# 260116710xxxx-HW-V2_0.net
KiCad netlist of a schematic drawn in EAGLE
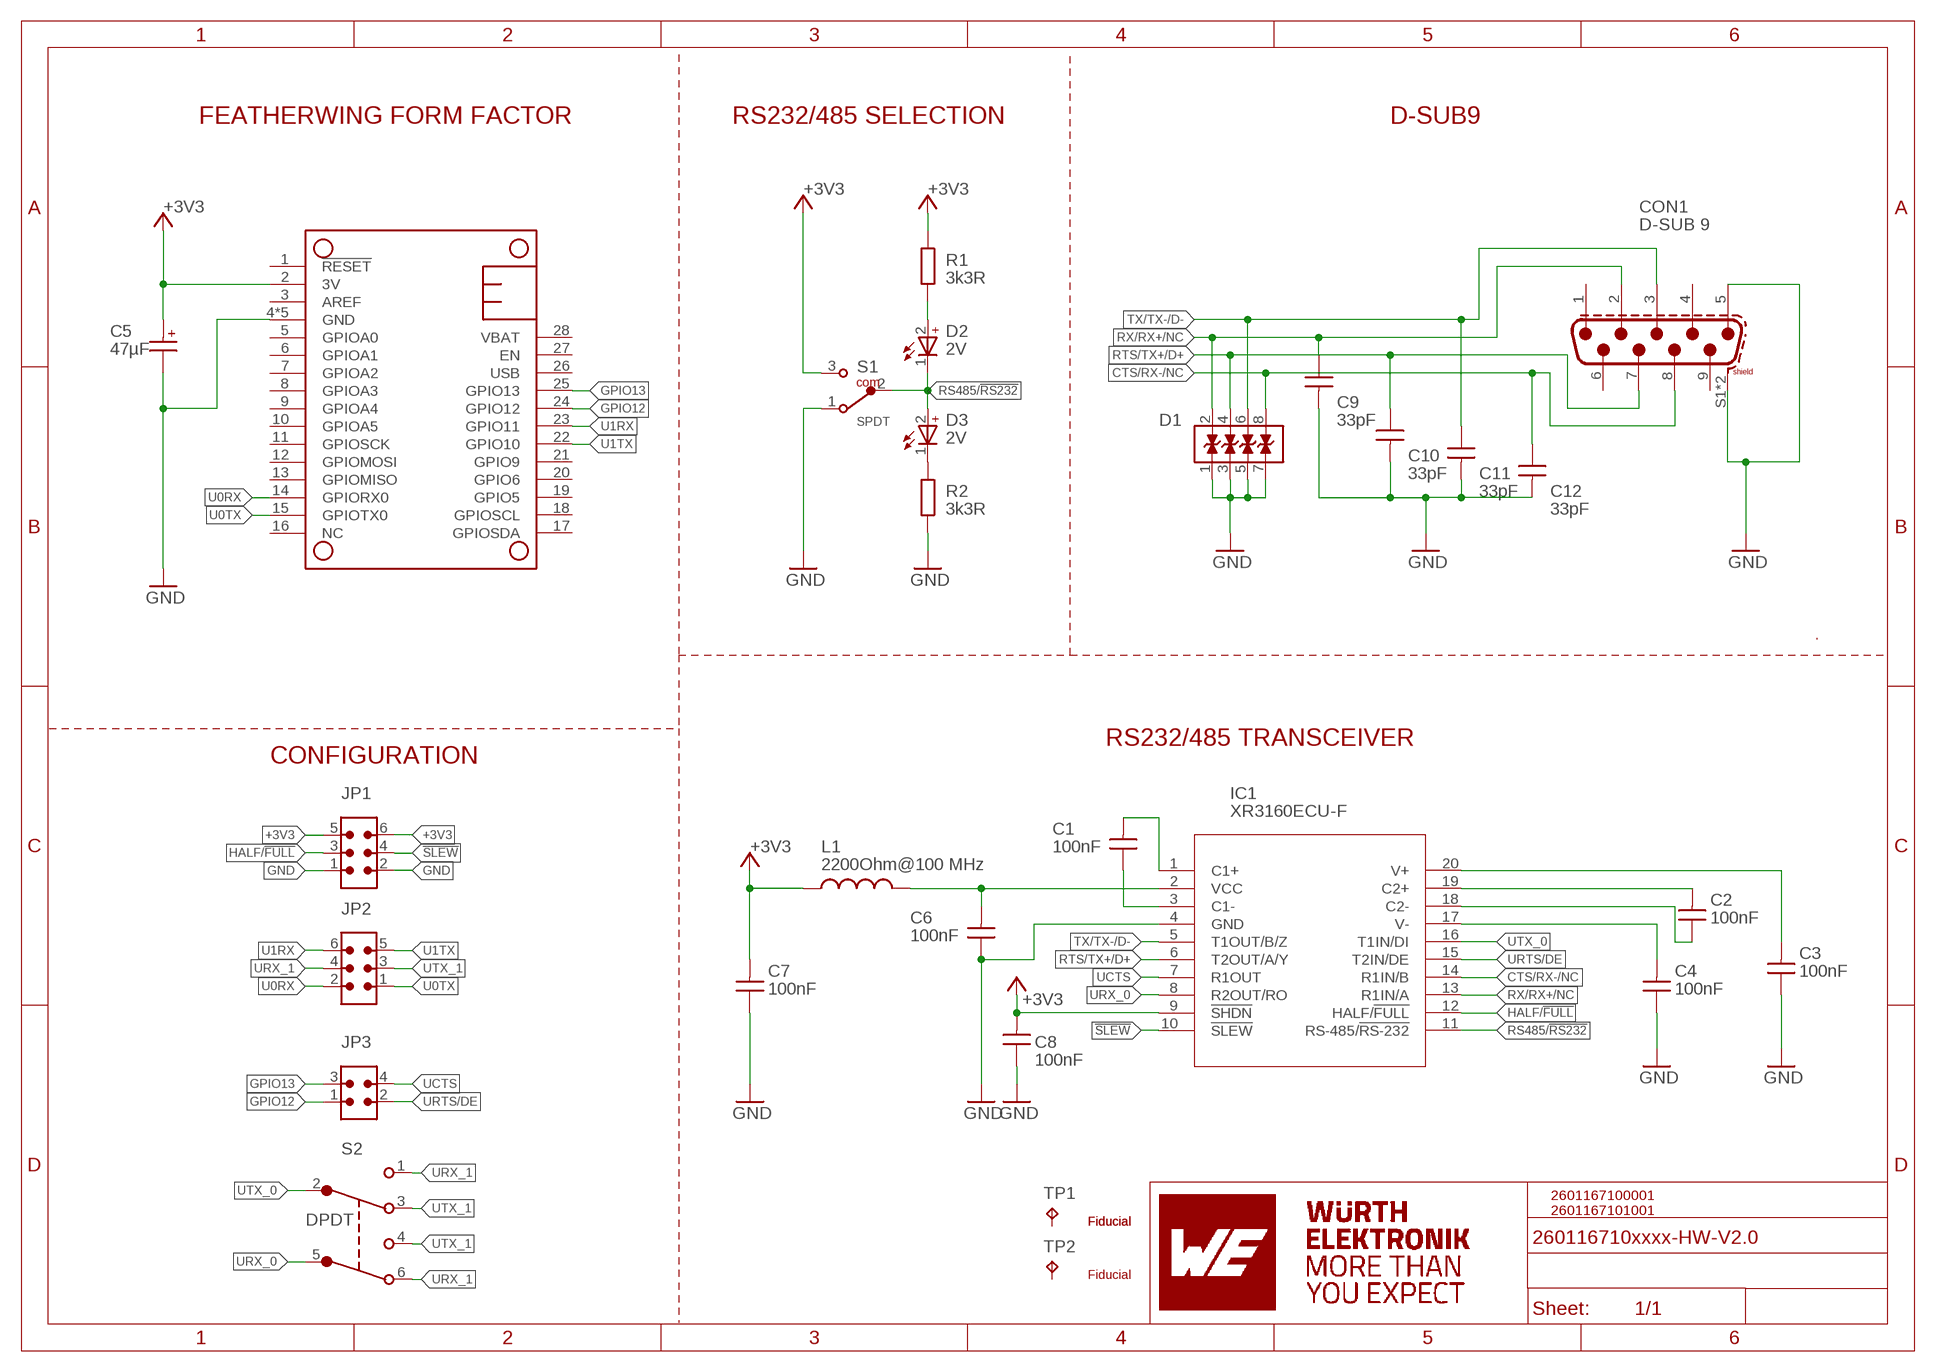
[diagram p0: schematic, sheet 1]

(export (version "E")
  (design (tool "Eeschema 10.0.6"))
  (components
    (comp (ref "C1")
      (value "100nF")
      (footprint "eagle-import:WCAP-CSGP_0603_W")
      (libsource (lib "eagle-import") (part "WCAP-CSGP_Rev21e_WCAP-CSGP_0603_10V(DC)_W_885012206020"))
    )
    (comp (ref "C2")
      (value "100nF")
      (footprint "eagle-import:WCAP-CSGP_0603_W")
      (libsource (lib "eagle-import") (part "WCAP-CSGP_Rev21e_WCAP-CSGP_0603_10V(DC)_W_885012206020"))
    )
    (comp (ref "C3")
      (value "100nF")
      (footprint "eagle-import:WCAP-CSGP_0603_W")
      (libsource (lib "eagle-import") (part "WCAP-CSGP_Rev21e_WCAP-CSGP_0603_10V(DC)_W_885012206020"))
    )
    (comp (ref "C4")
      (value "100nF")
      (footprint "eagle-import:WCAP-CSGP_0603_W")
      (libsource (lib "eagle-import") (part "WCAP-CSGP_Rev21e_WCAP-CSGP_0603_10V(DC)_W_885012206020"))
    )
    (comp (ref "C5")
      (value "47µF")
      (footprint "eagle-import:WCAP-AS5H_5X5.5(DXL)")
      (libsource (lib "eagle-import") (part "WCAP-AS5H_5X5.5_865230142003"))
    )
    (comp (ref "C6")
      (value "100nF")
      (footprint "eagle-import:WCAP-CSGP_0603_W")
      (libsource (lib "eagle-import") (part "WCAP-CSGP_Rev21e_WCAP-CSGP_0603_10V(DC)_W_885012206020"))
    )
    (comp (ref "C7")
      (value "100nF")
      (footprint "eagle-import:WCAP-CSGP_0603_W")
      (libsource (lib "eagle-import") (part "WCAP-CSGP_Rev21e_WCAP-CSGP_0603_10V(DC)_W_885012206020"))
    )
    (comp (ref "C8")
      (value "100nF")
      (footprint "eagle-import:WCAP-CSGP_0603_W")
      (libsource (lib "eagle-import") (part "WCAP-CSGP_Rev21e_WCAP-CSGP_0603_10V(DC)_W_885012206020"))
    )
    (comp (ref "C9")
      (value "33pF")
      (footprint "eagle-import:WCAP-CSGP_0603_W")
      (libsource (lib "eagle-import") (part "WCAP-CSGP_0603_25V(DC)_W_885012006035"))
    )
    (comp (ref "C10")
      (value "33pF")
      (footprint "eagle-import:WCAP-CSGP_0603_W")
      (libsource (lib "eagle-import") (part "WCAP-CSGP_0603_25V(DC)_W_885012006035"))
    )
    (comp (ref "C11")
      (value "33pF")
      (footprint "eagle-import:WCAP-CSGP_0603_W")
      (libsource (lib "eagle-import") (part "WCAP-CSGP_0603_25V(DC)_W_885012006035"))
    )
    (comp (ref "C12")
      (value "33pF")
      (footprint "eagle-import:WCAP-CSGP_0603_W")
      (libsource (lib "eagle-import") (part "WCAP-CSGP_0603_25V(DC)_W_885012006035"))
    )
    (comp (ref "CON1")
      (value "D-SUB 9")
      (footprint "eagle-import:618009231221")
      (libsource (lib "eagle-import") (part "6180XX231221_618009231221"))
    )
    (comp (ref "D1")
      (value "18V")
      (footprint "eagle-import:WE-VEA_0612")
      (libsource (lib "eagle-import") (part "WE-VEA_0612_82380180121"))
    )
    (comp (ref "D2")
      (value "2V")
      (footprint "eagle-import:WL-SMCW_0603")
      (libsource (lib "eagle-import") (part "WL-SMCW_0603_150060AS75000"))
    )
    (comp (ref "D3")
      (value "2V")
      (footprint "eagle-import:WL-SMCW_0603")
      (libsource (lib "eagle-import") (part "WL-SMCW_0603_150060AS75000"))
    )
    (comp (ref "IC1")
      (value "XR3160ECU-F")
      (footprint "eagle-import:SSOP-20")
      (fields (field (name "COPYRIGHT") "Copyright (C) 2021 Ultra Librarian. All rights reserved."))
      (libsource (lib "eagle-import") (part "XR3160ECU-F"))
    )
    (comp (ref "JP1")
      (value "61300621121")
      (footprint "eagle-import:61300621121")
      (libsource (lib "eagle-import") (part "6130XX21121_61300621121"))
    )
    (comp (ref "JP2")
      (value "61300621121")
      (footprint "eagle-import:61300621121")
      (libsource (lib "eagle-import") (part "6130XX21121_61300621121"))
    )
    (comp (ref "JP3")
      (value "61300421121")
      (footprint "eagle-import:61300421121")
      (libsource (lib "eagle-import") (part "6130XX21121_61300421121"))
    )
    (comp (ref "L1")
      (value "2200Ohm@100 MHz")
      (footprint "eagle-import:WE-CBF_0603(W=2.2)")
      (libsource (lib "eagle-import") (part "WE-CBF_0603_WB_HS_742792693"))
    )
    (comp (ref "MS1")
      (value "FEATHERWING_WIDE")
      (footprint "eagle-import:FEATHERWING_WIDE")
      (fields (field (name "COMMENT") "Kit containing 2 headers") (field (name "MANUFACTURER") "Adafruit"))
      (libsource (lib "eagle-import") (part "FEATHERWING_WIDE"))
    )
    (comp (ref "R1")
      (value "3k3R")
      (footprint "eagle-import:R0603")
      (libsource (lib "eagle-import") (part "R-EU_R0603"))
    )
    (comp (ref "R2")
      (value "3k3R")
      (footprint "eagle-import:R0603")
      (libsource (lib "eagle-import") (part "R-EU_R0603"))
    )
    (comp (ref "S1")
      (value "SPDT")
      (footprint "eagle-import:450404015514")
      (libsource (lib "eagle-import") (part "450404015514"))
    )
    (comp (ref "S2")
      (value "DPDT")
      (footprint "eagle-import:452403012014")
      (libsource (lib "eagle-import") (part "452403012014"))
    )
    (comp (ref "TP1")
      (value "TPB1,27")
      (footprint "eagle-import:B1,27")
      (libsource (lib "eagle-import") (part "TPB1,27"))
    )
    (comp (ref "TP2")
      (value "TPB1,27")
      (footprint "eagle-import:B1,27")
      (libsource (lib "eagle-import") (part "TPB1,27"))
    )
  )
  (nets
    (net (code "1") (name "+3V3") (class "Default")
      (node (ref "C5") (pin "1") (pinfunction "+_1") (pintype "passive"))
      (node (ref "C7") (pin "2") (pinfunction "2_2") (pintype "passive"))
      (node (ref "C8") (pin "2") (pinfunction "2_2") (pintype "passive"))
      (node (ref "IC1") (pin "9") (pinfunction "~{SHDN}_9") (pintype "passive"))
      (node (ref "JP1") (pin "5") (pinfunction "5_5") (pintype "passive"))
      (node (ref "JP1") (pin "6") (pinfunction "6_6") (pintype "passive"))
      (node (ref "L1") (pin "2") (pinfunction "2_2") (pintype "passive"))
      (node (ref "MS1") (pin "2") (pinfunction "3V_2") (pintype "power_in"))
      (node (ref "R1") (pin "1") (pinfunction "1_1") (pintype "passive"))
      (node (ref "S1") (pin "3") (pinfunction "3_3") (pintype "passive"))
    )
    (net (code "2") (name "/HALF{slash}~{FULL}") (class "Default")
      (node (ref "IC1") (pin "12") (pinfunction "HALF/~{FULL}_12") (pintype "passive"))
      (node (ref "JP1") (pin "3") (pinfunction "3_3") (pintype "passive"))
    )
    (net (code "3") (name "/RS485{slash}~{RS232}") (class "Default")
      (node (ref "D2") (pin "1") (pinfunction "-_1") (pintype "passive"))
      (node (ref "D3") (pin "2") (pinfunction "+_2") (pintype "passive"))
      (node (ref "IC1") (pin "11") (pinfunction "RS-485/~{RS-232}_11") (pintype "passive"))
      (node (ref "S1") (pin "2") (pinfunction "2_2") (pintype "passive"))
    )
    (net (code "4") (name "/USB") (class "Default")
      (node (ref "MS1") (pin "26") (pinfunction "USB_26") (pintype "power_in"))
    )
    (net (code "5") (name "/VBAT") (class "Default")
      (node (ref "MS1") (pin "28") (pinfunction "VBAT_28") (pintype "power_in"))
    )
    (net (code "6") (name "/~{SLEW}") (class "Default")
      (node (ref "IC1") (pin "10") (pinfunction "~{SLEW}_10") (pintype "passive"))
      (node (ref "JP1") (pin "4") (pinfunction "4_4") (pintype "passive"))
    )
    (net (code "7") (name "CTS{slash}RX-{slash}NC") (class "Default")
      (node (ref "C12") (pin "1") (pinfunction "1_1") (pintype "passive"))
      (node (ref "CON1") (pin "8") (pinfunction "8_8") (pintype "bidirectional"))
      (node (ref "D1") (pin "8") (pinfunction "5_8") (pintype "passive"))
      (node (ref "IC1") (pin "14") (pinfunction "R1IN/B_14") (pintype "input"))
    )
    (net (code "8") (name "GND") (class "Default")
      (node (ref "C10") (pin "2") (pinfunction "2_2") (pintype "passive"))
      (node (ref "C11") (pin "2") (pinfunction "2_2") (pintype "passive"))
      (node (ref "C12") (pin "2") (pinfunction "2_2") (pintype "passive"))
      (node (ref "C3") (pin "1") (pinfunction "1_1") (pintype "passive"))
      (node (ref "C4") (pin "1") (pinfunction "1_1") (pintype "passive"))
      (node (ref "C5") (pin "2") (pinfunction "-_2") (pintype "passive"))
      (node (ref "C6") (pin "1") (pinfunction "1_1") (pintype "passive"))
      (node (ref "C7") (pin "1") (pinfunction "1_1") (pintype "passive"))
      (node (ref "C8") (pin "1") (pinfunction "1_1") (pintype "passive"))
      (node (ref "C9") (pin "2") (pinfunction "2_2") (pintype "passive"))
      (node (ref "CON1") (pin "5") (pinfunction "5_5") (pintype "bidirectional"))
      (node (ref "CON1") (pin "S1") (pinfunction "SHIELD_S1") (pintype "bidirectional"))
      (node (ref "CON1") (pin "S2") (pinfunction "SHIELD_S2") (pintype "bidirectional"))
      (node (ref "D1") (pin "1") (pinfunction "1_1") (pintype "passive"))
      (node (ref "D1") (pin "3") (pinfunction "2_3") (pintype "passive"))
      (node (ref "D1") (pin "5") (pinfunction "3_5") (pintype "passive"))
      (node (ref "D1") (pin "7") (pinfunction "4_7") (pintype "passive"))
      (node (ref "IC1") (pin "4") (pinfunction "GND_4") (pintype "power_in"))
      (node (ref "JP1") (pin "1") (pinfunction "1_1") (pintype "passive"))
      (node (ref "JP1") (pin "2") (pinfunction "2_2") (pintype "passive"))
      (node (ref "MS1") (pin "4") (pinfunction "GND_4") (pintype "power_in"))
      (node (ref "MS1") (pin "GND@0") (pinfunction "GND_GND@0") (pintype "power_in"))
      (node (ref "MS1") (pin "GND@1") (pinfunction "GND_GND@1") (pintype "power_in"))
      (node (ref "MS1") (pin "GND@2") (pinfunction "GND_GND@2") (pintype "power_in"))
      (node (ref "MS1") (pin "GND@3") (pinfunction "GND_GND@3") (pintype "power_in"))
      (node (ref "R2") (pin "1") (pinfunction "1_1") (pintype "passive"))
      (node (ref "S1") (pin "1") (pinfunction "1_1") (pintype "passive"))
    )
    (net (code "9") (name "GPIO12") (class "Default")
      (node (ref "JP3") (pin "1") (pinfunction "1_1") (pintype "passive"))
      (node (ref "MS1") (pin "24") (pinfunction "GPIO12_24") (pintype "bidirectional"))
    )
    (net (code "10") (name "GPIO13") (class "Default")
      (node (ref "JP3") (pin "3") (pinfunction "3_3") (pintype "passive"))
      (node (ref "MS1") (pin "25") (pinfunction "GPIO13_25") (pintype "bidirectional"))
    )
    (net (code "11") (name "Net-(D2-+)") (class "Default")
      (node (ref "D2") (pin "2") (pinfunction "+_2") (pintype "passive"))
      (node (ref "R1") (pin "2") (pinfunction "2_2") (pintype "passive"))
    )
    (net (code "12") (name "Net-(D3--)") (class "Default")
      (node (ref "D3") (pin "1") (pinfunction "-_1") (pintype "passive"))
      (node (ref "R2") (pin "2") (pinfunction "2_2") (pintype "passive"))
    )
    (net (code "13") (name "Net-(IC1-C1+)") (class "Default")
      (node (ref "C1") (pin "2") (pinfunction "2_2") (pintype "passive"))
      (node (ref "IC1") (pin "1") (pinfunction "C1+_1") (pintype "passive"))
    )
    (net (code "14") (name "Net-(IC1-C1-)") (class "Default")
      (node (ref "C1") (pin "1") (pinfunction "1_1") (pintype "passive"))
      (node (ref "IC1") (pin "3") (pinfunction "C1-_3") (pintype "passive"))
    )
    (net (code "15") (name "Net-(IC1-C2+)") (class "Default")
      (node (ref "C2") (pin "2") (pinfunction "2_2") (pintype "passive"))
      (node (ref "IC1") (pin "19") (pinfunction "C2+_19") (pintype "passive"))
    )
    (net (code "16") (name "Net-(IC1-C2-)") (class "Default")
      (node (ref "C2") (pin "1") (pinfunction "1_1") (pintype "passive"))
      (node (ref "IC1") (pin "18") (pinfunction "C2-_18") (pintype "passive"))
    )
    (net (code "17") (name "Net-(IC1-V+)") (class "Default")
      (node (ref "C3") (pin "2") (pinfunction "2_2") (pintype "passive"))
      (node (ref "IC1") (pin "20") (pinfunction "V+_20") (pintype "power_in"))
    )
    (net (code "18") (name "Net-(IC1-V-)") (class "Default")
      (node (ref "C4") (pin "2") (pinfunction "2_2") (pintype "passive"))
      (node (ref "IC1") (pin "17") (pinfunction "V-_17") (pintype "power_in"))
    )
    (net (code "19") (name "Net-(IC1-VCC)") (class "Default")
      (node (ref "C6") (pin "2") (pinfunction "2_2") (pintype "passive"))
      (node (ref "IC1") (pin "2") (pinfunction "VCC_2") (pintype "power_in"))
      (node (ref "L1") (pin "1") (pinfunction "1_1") (pintype "passive"))
    )
    (net (code "20") (name "RTS{slash}TX+{slash}D+") (class "Default")
      (node (ref "C10") (pin "1") (pinfunction "1_1") (pintype "passive"))
      (node (ref "CON1") (pin "7") (pinfunction "7_7") (pintype "bidirectional"))
      (node (ref "D1") (pin "4") (pinfunction "7_4") (pintype "passive"))
      (node (ref "IC1") (pin "6") (pinfunction "T2OUT/A/Y_6") (pintype "bidirectional"))
    )
    (net (code "21") (name "RX{slash}RX+{slash}NC") (class "Default")
      (node (ref "C9") (pin "1") (pinfunction "1_1") (pintype "passive"))
      (node (ref "CON1") (pin "2") (pinfunction "2_2") (pintype "bidirectional"))
      (node (ref "D1") (pin "2") (pinfunction "8_2") (pintype "passive"))
      (node (ref "IC1") (pin "13") (pinfunction "R1IN/A_13") (pintype "input"))
    )
    (net (code "22") (name "TX{slash}TX-{slash}D-") (class "Default")
      (node (ref "C11") (pin "1") (pinfunction "1_1") (pintype "passive"))
      (node (ref "CON1") (pin "3") (pinfunction "3_3") (pintype "bidirectional"))
      (node (ref "D1") (pin "6") (pinfunction "6_6") (pintype "passive"))
      (node (ref "IC1") (pin "5") (pinfunction "T1OUT/B/Z_5") (pintype "bidirectional"))
    )
    (net (code "23") (name "U0RX") (class "Default")
      (node (ref "JP2") (pin "2") (pinfunction "2_2") (pintype "passive"))
      (node (ref "MS1") (pin "14") (pinfunction "GPIORX0_14") (pintype "bidirectional"))
    )
    (net (code "24") (name "U0TX") (class "Default")
      (node (ref "JP2") (pin "1") (pinfunction "1_1") (pintype "passive"))
      (node (ref "MS1") (pin "15") (pinfunction "GPIOTX0_15") (pintype "bidirectional"))
    )
    (net (code "25") (name "U1RX") (class "Default")
      (node (ref "JP2") (pin "6") (pinfunction "6_6") (pintype "passive"))
      (node (ref "MS1") (pin "23") (pinfunction "GPIO11_23") (pintype "bidirectional"))
    )
    (net (code "26") (name "U1TX") (class "Default")
      (node (ref "JP2") (pin "5") (pinfunction "5_5") (pintype "passive"))
      (node (ref "MS1") (pin "22") (pinfunction "GPIO10_22") (pintype "bidirectional"))
    )
    (net (code "27") (name "UCTS") (class "Default")
      (node (ref "IC1") (pin "7") (pinfunction "R1OUT_7") (pintype "output"))
      (node (ref "JP3") (pin "4") (pinfunction "4_4") (pintype "passive"))
    )
    (net (code "28") (name "URTS{slash}DE") (class "Default")
      (node (ref "IC1") (pin "15") (pinfunction "T2IN/DE_15") (pintype "input"))
      (node (ref "JP3") (pin "2") (pinfunction "2_2") (pintype "passive"))
    )
    (net (code "29") (name "URX_0") (class "Default")
      (node (ref "IC1") (pin "8") (pinfunction "R2OUT/RO_8") (pintype "output"))
      (node (ref "S2") (pin "5") (pinfunction "5_5") (pintype "passive"))
    )
    (net (code "30") (name "URX_1") (class "Default")
      (node (ref "JP2") (pin "4") (pinfunction "4_4") (pintype "passive"))
      (node (ref "S2") (pin "1") (pinfunction "1_1") (pintype "passive"))
      (node (ref "S2") (pin "6") (pinfunction "6_6") (pintype "passive"))
    )
    (net (code "31") (name "UTX_0") (class "Default")
      (node (ref "IC1") (pin "16") (pinfunction "T1IN/DI_16") (pintype "input"))
      (node (ref "S2") (pin "2") (pinfunction "2_2") (pintype "passive"))
    )
    (net (code "32") (name "UTX_1") (class "Default")
      (node (ref "JP2") (pin "3") (pinfunction "3_3") (pintype "passive"))
      (node (ref "S2") (pin "3") (pinfunction "3_3") (pintype "passive"))
      (node (ref "S2") (pin "4") (pinfunction "4_4") (pintype "passive"))
    )
    (net (code "33") (name "unconnected-(CON1-Pad1)") (class "Default")
      (node (ref "CON1") (pin "1") (pinfunction "1_1") (pintype "bidirectional"))
    )
    (net (code "34") (name "unconnected-(CON1-Pad4)") (class "Default")
      (node (ref "CON1") (pin "4") (pinfunction "4_4") (pintype "bidirectional"))
    )
    (net (code "35") (name "unconnected-(CON1-Pad6)") (class "Default")
      (node (ref "CON1") (pin "6") (pinfunction "6_6") (pintype "bidirectional"))
    )
    (net (code "36") (name "unconnected-(CON1-Pad9)") (class "Default")
      (node (ref "CON1") (pin "9") (pinfunction "9_9") (pintype "bidirectional"))
    )
    (net (code "37") (name "unconnected-(MS1-AREF-Pad3)") (class "Default")
      (node (ref "MS1") (pin "3") (pinfunction "AREF_3") (pintype "passive"))
    )
    (net (code "38") (name "unconnected-(MS1-EN-Pad27)") (class "Default")
      (node (ref "MS1") (pin "27") (pinfunction "EN_27") (pintype "passive"))
    )
    (net (code "39") (name "unconnected-(MS1-GPIO5-Pad19)") (class "Default")
      (node (ref "MS1") (pin "19") (pinfunction "GPIO5_19") (pintype "bidirectional"))
    )
    (net (code "40") (name "unconnected-(MS1-GPIO6-Pad20)") (class "Default")
      (node (ref "MS1") (pin "20") (pinfunction "GPIO6_20") (pintype "bidirectional"))
    )
    (net (code "41") (name "unconnected-(MS1-GPIO9-Pad21)") (class "Default")
      (node (ref "MS1") (pin "21") (pinfunction "GPIO9_21") (pintype "bidirectional"))
    )
    (net (code "42") (name "unconnected-(MS1-GPIOA0-Pad5)") (class "Default")
      (node (ref "MS1") (pin "5") (pinfunction "GPIOA0_5") (pintype "bidirectional"))
    )
    (net (code "43") (name "unconnected-(MS1-GPIOA1-Pad6)") (class "Default")
      (node (ref "MS1") (pin "6") (pinfunction "GPIOA1_6") (pintype "bidirectional"))
    )
    (net (code "44") (name "unconnected-(MS1-GPIOA2-Pad7)") (class "Default")
      (node (ref "MS1") (pin "7") (pinfunction "GPIOA2_7") (pintype "bidirectional"))
    )
    (net (code "45") (name "unconnected-(MS1-GPIOA3-Pad8)") (class "Default")
      (node (ref "MS1") (pin "8") (pinfunction "GPIOA3_8") (pintype "bidirectional"))
    )
    (net (code "46") (name "unconnected-(MS1-GPIOA4-Pad9)") (class "Default")
      (node (ref "MS1") (pin "9") (pinfunction "GPIOA4_9") (pintype "bidirectional"))
    )
    (net (code "47") (name "unconnected-(MS1-GPIOA5-Pad10)") (class "Default")
      (node (ref "MS1") (pin "10") (pinfunction "GPIOA5_10") (pintype "bidirectional"))
    )
    (net (code "48") (name "unconnected-(MS1-GPIOMISO-Pad13)") (class "Default")
      (node (ref "MS1") (pin "13") (pinfunction "GPIOMISO_13") (pintype "bidirectional"))
    )
    (net (code "49") (name "unconnected-(MS1-GPIOMOSI-Pad12)") (class "Default")
      (node (ref "MS1") (pin "12") (pinfunction "GPIOMOSI_12") (pintype "bidirectional"))
    )
    (net (code "50") (name "unconnected-(MS1-GPIOSCK-Pad11)") (class "Default")
      (node (ref "MS1") (pin "11") (pinfunction "GPIOSCK_11") (pintype "bidirectional"))
    )
    (net (code "51") (name "unconnected-(MS1-GPIOSCL-Pad18)") (class "Default")
      (node (ref "MS1") (pin "18") (pinfunction "GPIOSCL_18") (pintype "bidirectional"))
    )
    (net (code "52") (name "unconnected-(MS1-GPIOSDA-Pad17)") (class "Default")
      (node (ref "MS1") (pin "17") (pinfunction "GPIOSDA_17") (pintype "bidirectional"))
    )
    (net (code "53") (name "unconnected-(MS1-NC-Pad16)") (class "Default")
      (node (ref "MS1") (pin "16") (pinfunction "NC_16") (pintype "passive"))
    )
    (net (code "54") (name "unconnected-(MS1-~{RESET}-Pad1)") (class "Default")
      (node (ref "MS1") (pin "1") (pinfunction "~{RESET}_1") (pintype "no_connect"))
    )
    (net (code "55") (name "unconnected-(TP1-PadTP)") (class "Default")
      (node (ref "TP1") (pin "TP") (pinfunction "TP_TP") (pintype "input"))
    )
    (net (code "56") (name "unconnected-(TP2-PadTP)") (class "Default")
      (node (ref "TP2") (pin "TP") (pinfunction "TP_TP") (pintype "input"))
    )
  )
)
